# Sheet.net
KiCad netlist of a schematic drawn in Altium Designer
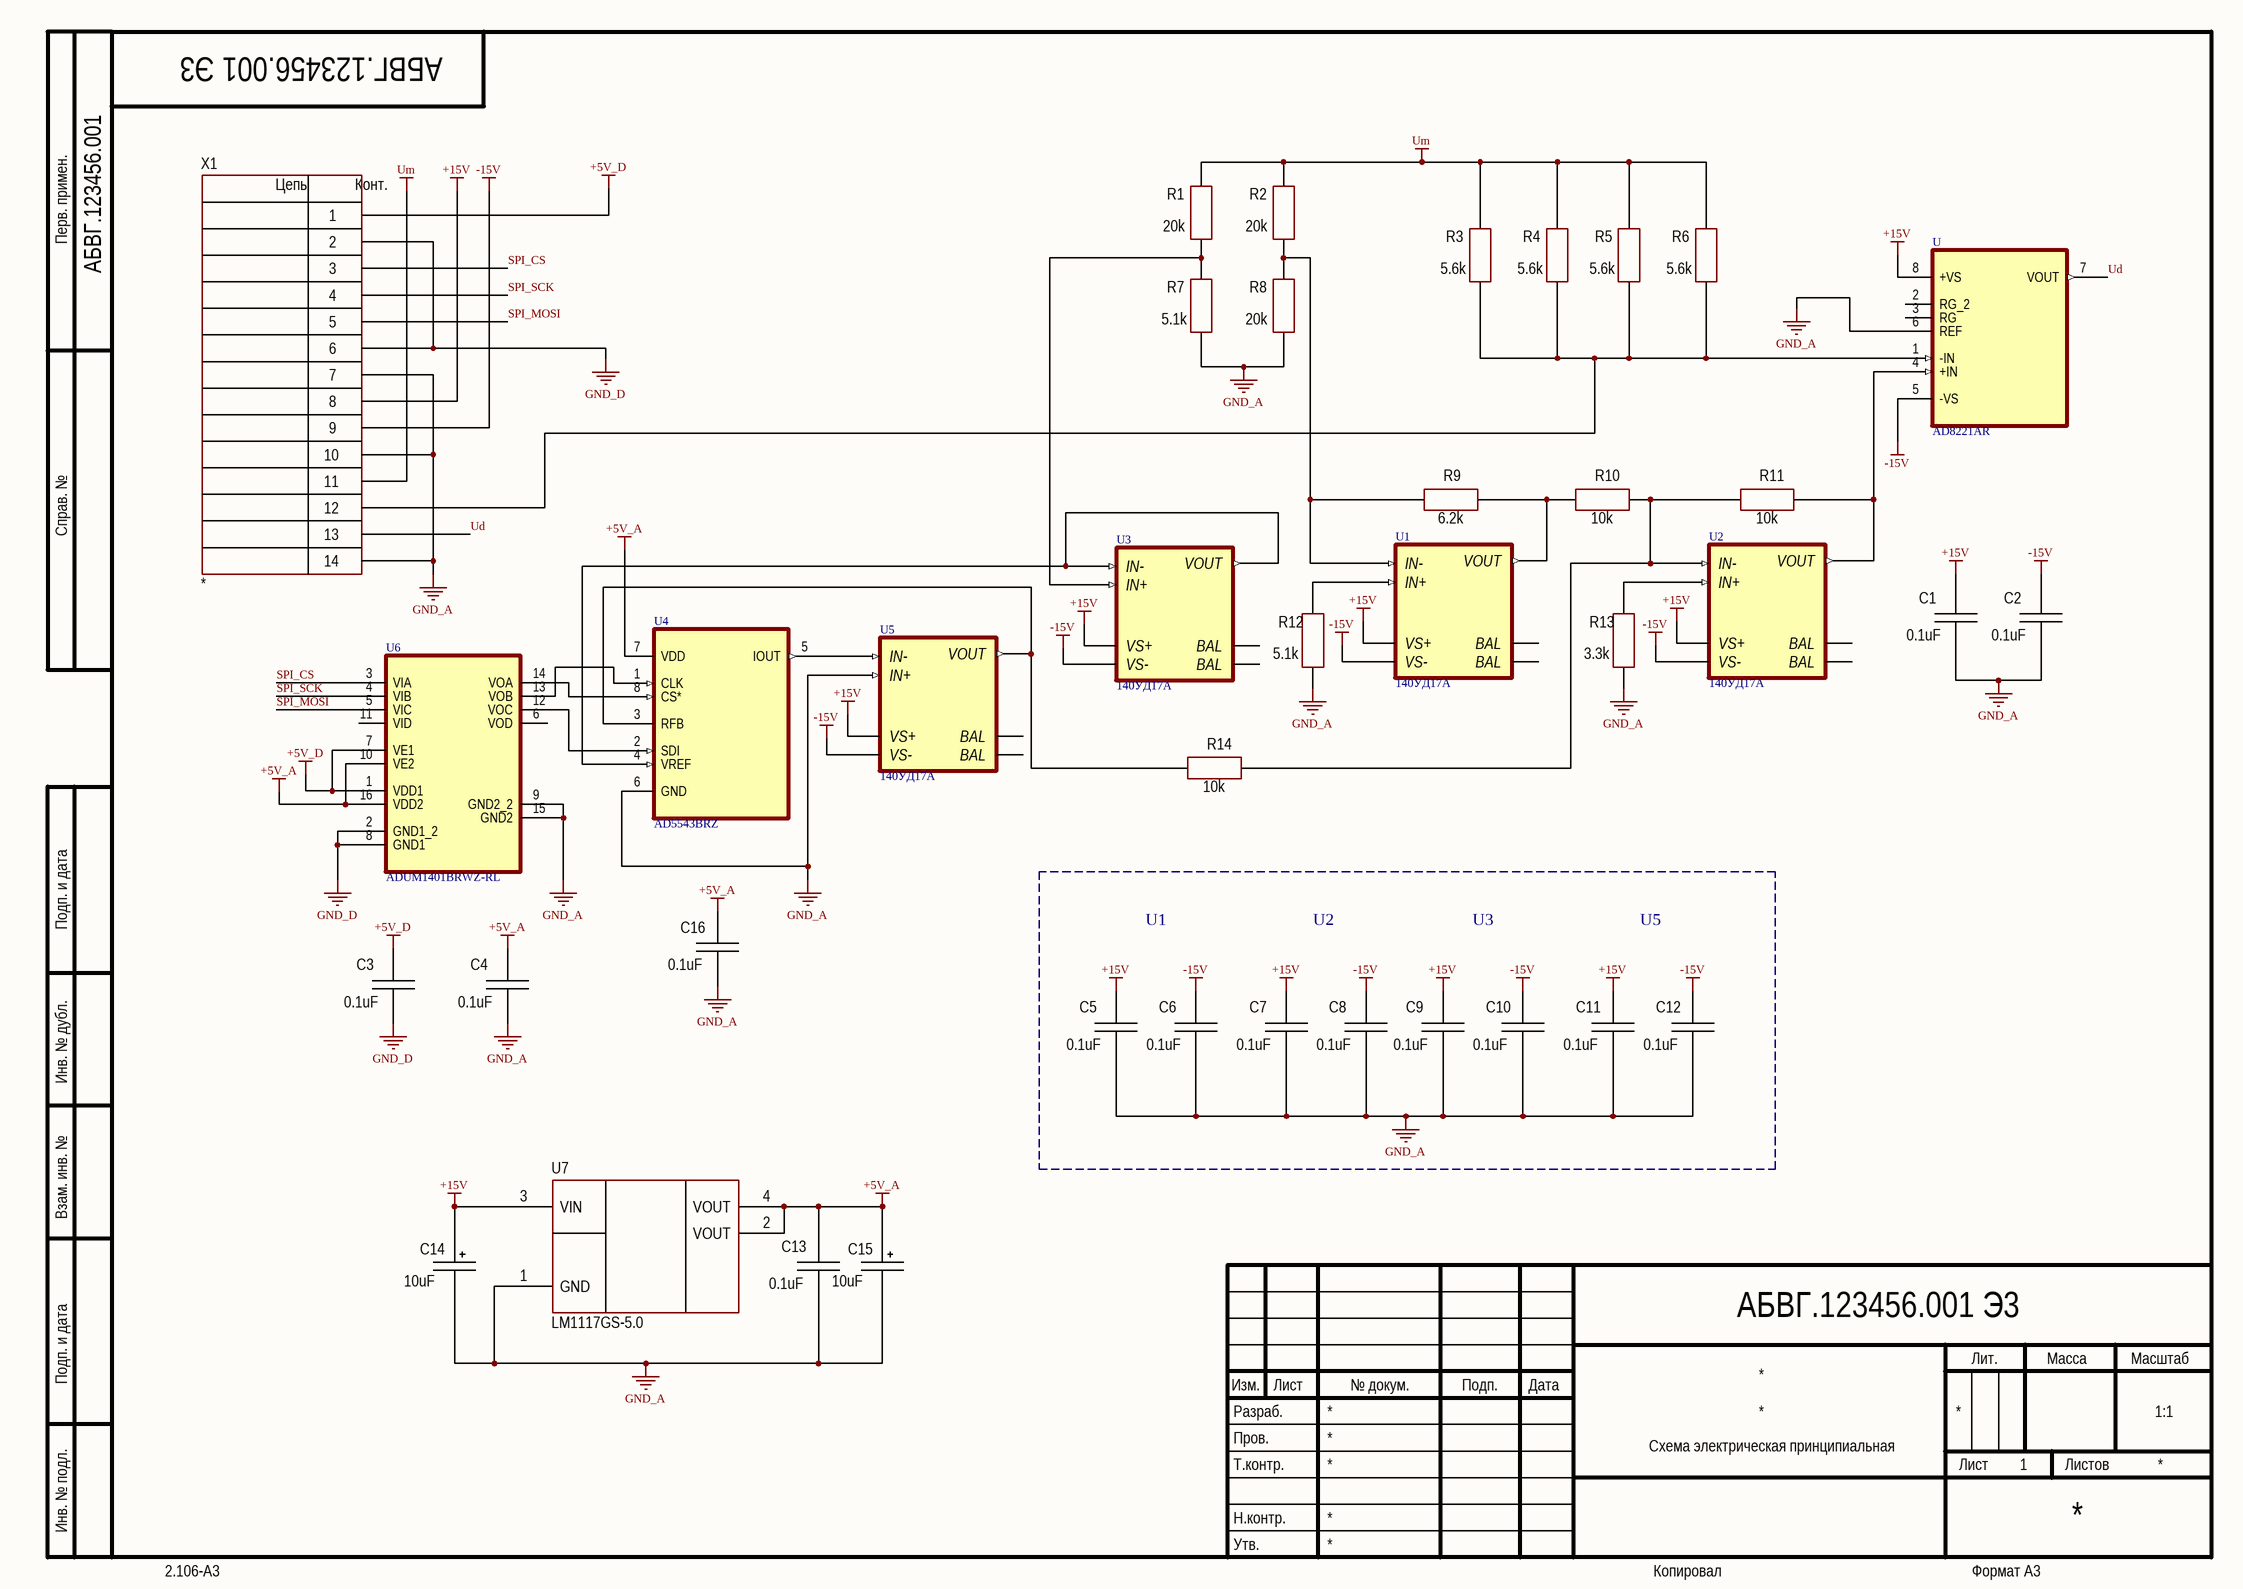
[diagram p0: Sheet.SchDoc]

(export (version "E")
  (design (tool "Eeschema 10.0.6"))
  (components
    (comp (ref "C1")
      (value "0.1uF")
      (footprint "standard:CH1206C")
      (libsource (lib "Discrete") (part "Capacitor"))
    )
    (comp (ref "C2")
      (value "0.1uF")
      (footprint "standard:CH1206C")
      (libsource (lib "Discrete") (part "Capacitor"))
    )
    (comp (ref "C3")
      (value "0.1uF")
      (footprint "standard:CH1206C")
      (libsource (lib "Discrete") (part "Capacitor"))
    )
    (comp (ref "C4")
      (value "0.1uF")
      (footprint "standard:CH1206C")
      (libsource (lib "Discrete") (part "Capacitor"))
    )
    (comp (ref "C5")
      (value "0.1uF")
      (footprint "standard:CH1206C")
      (libsource (lib "Discrete") (part "Capacitor"))
    )
    (comp (ref "C6")
      (value "0.1uF")
      (footprint "standard:CH1206C")
      (libsource (lib "Discrete") (part "Capacitor"))
    )
    (comp (ref "C7")
      (value "0.1uF")
      (footprint "standard:CH1206C")
      (libsource (lib "Discrete") (part "Capacitor"))
    )
    (comp (ref "C8")
      (value "0.1uF")
      (footprint "standard:CH1206C")
      (libsource (lib "Discrete") (part "Capacitor"))
    )
    (comp (ref "C9")
      (value "0.1uF")
      (footprint "standard:CH1206C")
      (libsource (lib "Discrete") (part "Capacitor"))
    )
    (comp (ref "C10")
      (value "0.1uF")
      (footprint "standard:CH1206C")
      (libsource (lib "Discrete") (part "Capacitor"))
    )
    (comp (ref "C11")
      (value "0.1uF")
      (footprint "standard:CH1206C")
      (libsource (lib "Discrete") (part "Capacitor"))
    )
    (comp (ref "C12")
      (value "0.1uF")
      (footprint "standard:CH1206C")
      (libsource (lib "Discrete") (part "Capacitor"))
    )
    (comp (ref "C13")
      (value "0.1uF")
      (footprint "standard:CH1206C")
      (libsource (lib "Discrete") (part "Capacitor"))
    )
    (comp (ref "C14")
      (value "10uF")
      (footprint "standard:TANTAL_A")
      (libsource (lib "Discrete") (part "TantalCap"))
    )
    (comp (ref "C15")
      (value "10uF")
      (footprint "standard:TANTAL_A")
      (libsource (lib "Discrete") (part "TantalCap"))
    )
    (comp (ref "C16")
      (value "0.1uF")
      (footprint "standard:CH1206C")
      (libsource (lib "Discrete") (part "Capacitor"))
    )
    (comp (ref "R1") (value "20k") (footprint "standard:CH1206R") (libsource (lib "") (part "Resistor_2")))
    (comp (ref "R2") (value "20k") (footprint "standard:CH1206R") (libsource (lib "") (part "Resistor_2")))
    (comp (ref "R3") (value "5.6k") (footprint "standard:CH1206R") (libsource (lib "") (part "Resistor_1")))
    (comp (ref "R4") (value "5.6k") (footprint "standard:CH1206R") (libsource (lib "") (part "Resistor_1")))
    (comp (ref "R5") (value "5.6k") (footprint "standard:CH1206R") (libsource (lib "") (part "Resistor_1")))
    (comp (ref "R6") (value "5.6k") (footprint "standard:CH1206R") (libsource (lib "") (part "Resistor_1")))
    (comp (ref "R7")
      (value "5.1k")
      (footprint "standard:CH1206R")
      (libsource (lib "Discrete") (part "Resistor"))
    )
    (comp (ref "R8")
      (value "20k")
      (footprint "standard:CH1206R")
      (libsource (lib "Discrete") (part "Resistor"))
    )
    (comp (ref "R9") (value "6.2k") (footprint "standard:CH1206R") (libsource (lib "") (part "Resistor_3")))
    (comp (ref "R10") (value "10k") (footprint "standard:CH1206R") (libsource (lib "") (part "Resistor_3")))
    (comp (ref "R11") (value "10k") (footprint "standard:CH1206R") (libsource (lib "") (part "Resistor_3")))
    (comp (ref "R12") (value "5.1k") (footprint "standard:CH1206R") (libsource (lib "") (part "Resistor_2")))
    (comp (ref "R13") (value "3.3k") (footprint "standard:CH1206R") (libsource (lib "") (part "Resistor_2")))
    (comp (ref "R14") (value "10k") (footprint "standard:CH1206R") (libsource (lib "") (part "Resistor_3")))
    (comp (ref "U")
      (value "AD8221AR")
      (footprint "SOIC127P600X175-8N")
      (description "Instrumentation Amplifier 1 Circuit 8-SOIC")
      (fields (field (name "MF") "Analog Devices") (field (name "MP") "AD8221BR"))
      (libsource (lib "AD8221BR") (part "AD8221BR"))
    )
    (comp (ref "U1")
      (value "140УД17А")
      (footprint "140УД17А")
      (description "Precision Op Amp")
      (libsource (lib "140УД17А") (part "140УД17А"))
    )
    (comp (ref "U2")
      (value "140УД17А")
      (footprint "140УД17А")
      (description "Precision Op Amp")
      (libsource (lib "") (part "140УД17А_1"))
    )
    (comp (ref "U3")
      (value "140УД17А")
      (footprint "140УД17А")
      (description "Precision Op Amp")
      (libsource (lib "") (part "140УД17А_1"))
    )
    (comp (ref "U4")
      (value "AD5543BRZ")
      (footprint "SOIC127P600X175-8N")
      (description "16 Bit Digital to Analog Converter 1 8-SOIC")
      (fields (field (name "MF") "Analog Devices"))
      (libsource (lib "AD5543BRZ") (part "AD5543BRZ"))
    )
    (comp (ref "U5")
      (value "140УД17А")
      (footprint "140УД17А")
      (description "Precision Op Amp")
      (libsource (lib "") (part "140УД17А_1"))
    )
    (comp (ref "U6")
      (value "ADUM1401BRWZ-RL")
      (footprint "SOIC127P1032X265-16N")
      (fields (field (name "MF") "Analog Devices"))
      (libsource (lib "ADUM1401BRWZ-RL") (part "ADUM1401BRWZ-RL"))
    )
    (comp (ref "U7")
      (value "~")
      (footprint "StandardCase:SOT223")
      (description "Linear voltage regulator")
      (fields
        (field (name "MANUFACTURER") "STMicroelectronics")
        (field (name "VALUEMANUFACTURERPARTNUMBER") "Linear voltage regulator, input 3.9...18V, 0.6V, output 3.3V, 1.2A, -40...+85°C, SOT223")
        (field (name "PARTNUMBER") "LM1117GS-5.0")
      )
      (libsource (lib "IC. Power supply") (part "LDL1117S33R"))
    )
    (comp (ref "X1")
      (value "*")
      (footprint "custom:CON: PLS-14")
      (libsource (lib "Connectors") (part "14-Connector"))
    )
  )
  (nets
    (net (code "1") (name "+5V_A") (class "Default")
      (node (ref "C13") (pin "2") (pinfunction "2_2") (pintype "power_in"))
      (node (ref "C15") (pin "1") (pinfunction "1_1") (pintype "power_in"))
      (node (ref "C16") (pin "2") (pinfunction "2_2") (pintype "power_in"))
      (node (ref "C4") (pin "2") (pinfunction "2_2") (pintype "power_in"))
      (node (ref "U4") (pin "7") (pinfunction "VDD_7") (pintype "power_in"))
      (node (ref "U6") (pin "10") (pinfunction "VE2_10") (pintype "passive"))
      (node (ref "U6") (pin "16") (pinfunction "VDD2_16") (pintype "power_in"))
      (node (ref "U7") (pin "2") (pinfunction "VOUT_2") (pintype "power_in"))
      (node (ref "U7") (pin "4") (pinfunction "VOUT_4") (pintype "power_in"))
    )
    (net (code "2") (name "+5V_D") (class "Default")
      (node (ref "C3") (pin "2") (pinfunction "2_2") (pintype "power_in"))
      (node (ref "U6") (pin "1") (pinfunction "VDD1_1") (pintype "power_in"))
      (node (ref "U6") (pin "7") (pinfunction "VE1_7") (pintype "passive"))
      (node (ref "X1") (pin "1") (pinfunction "1_1") (pintype "passive"))
    )
    (net (code "3") (name "+15V") (class "Default")
      (node (ref "C1") (pin "2") (pinfunction "2_2") (pintype "power_in"))
      (node (ref "C11") (pin "2") (pinfunction "2_2") (pintype "power_in"))
      (node (ref "C14") (pin "1") (pinfunction "1_1") (pintype "power_in"))
      (node (ref "C5") (pin "2") (pinfunction "2_2") (pintype "power_in"))
      (node (ref "C7") (pin "2") (pinfunction "2_2") (pintype "power_in"))
      (node (ref "C9") (pin "2") (pinfunction "2_2") (pintype "power_in"))
      (node (ref "U") (pin "8") (pinfunction "+VS_8") (pintype "power_in"))
      (node (ref "U1") (pin "8") (pinfunction "VS+_8") (pintype "power_in"))
      (node (ref "U2") (pin "8") (pinfunction "VS+_8") (pintype "power_in"))
      (node (ref "U3") (pin "8") (pinfunction "VS+_8") (pintype "power_in"))
      (node (ref "U5") (pin "8") (pinfunction "VS+_8") (pintype "power_in"))
      (node (ref "U7") (pin "3") (pinfunction "VIN_3") (pintype "power_in"))
      (node (ref "X1") (pin "8") (pinfunction "8_8") (pintype "power_in"))
    )
    (net (code "4") (name "-15V") (class "Default")
      (node (ref "C10") (pin "2") (pinfunction "2_2") (pintype "power_in"))
      (node (ref "C12") (pin "2") (pinfunction "2_2") (pintype "power_in"))
      (node (ref "C2") (pin "2") (pinfunction "2_2") (pintype "power_in"))
      (node (ref "C6") (pin "2") (pinfunction "2_2") (pintype "power_in"))
      (node (ref "C8") (pin "2") (pinfunction "2_2") (pintype "power_in"))
      (node (ref "U") (pin "5") (pinfunction "-VS_5") (pintype "power_in"))
      (node (ref "U1") (pin "5") (pinfunction "VS-_5") (pintype "power_in"))
      (node (ref "U2") (pin "5") (pinfunction "VS-_5") (pintype "power_in"))
      (node (ref "U3") (pin "5") (pinfunction "VS-_5") (pintype "power_in"))
      (node (ref "U5") (pin "5") (pinfunction "VS-_5") (pintype "power_in"))
      (node (ref "X1") (pin "9") (pinfunction "9_9") (pintype "power_in"))
    )
    (net (code "5") (name "/SPI_CS") (class "Default")
      (node (ref "U6") (pin "3") (pinfunction "VIA_3") (pintype "passive"))
      (node (ref "X1") (pin "3") (pinfunction "3_3") (pintype "power_in"))
    )
    (net (code "6") (name "/SPI_MOSI") (class "Default")
      (node (ref "U6") (pin "5") (pinfunction "VIC_5") (pintype "passive"))
      (node (ref "X1") (pin "5") (pinfunction "5_5") (pintype "power_in"))
    )
    (net (code "7") (name "/SPI_SCK") (class "Default")
      (node (ref "U6") (pin "4") (pinfunction "VIB_4") (pintype "passive"))
      (node (ref "X1") (pin "4") (pinfunction "4_4") (pintype "power_in"))
    )
    (net (code "8") (name "/Ud") (class "Default")
      (node (ref "U") (pin "7") (pinfunction "VOUT_7") (pintype "output"))
      (node (ref "X1") (pin "13") (pinfunction "13_13") (pintype "power_in"))
    )
    (net (code "9") (name "GND_A") (class "Default")
      (node (ref "C1") (pin "1") (pinfunction "1_1") (pintype "power_in"))
      (node (ref "C10") (pin "1") (pinfunction "1_1") (pintype "power_in"))
      (node (ref "C11") (pin "1") (pinfunction "1_1") (pintype "power_in"))
      (node (ref "C12") (pin "1") (pinfunction "1_1") (pintype "power_in"))
      (node (ref "C13") (pin "1") (pinfunction "1_1") (pintype "power_in"))
      (node (ref "C14") (pin "2") (pinfunction "2_2") (pintype "power_in"))
      (node (ref "C15") (pin "2") (pinfunction "2_2") (pintype "power_in"))
      (node (ref "C16") (pin "1") (pinfunction "1_1") (pintype "power_in"))
      (node (ref "C2") (pin "1") (pinfunction "1_1") (pintype "power_in"))
      (node (ref "C4") (pin "1") (pinfunction "1_1") (pintype "power_in"))
      (node (ref "C5") (pin "1") (pinfunction "1_1") (pintype "power_in"))
      (node (ref "C6") (pin "1") (pinfunction "1_1") (pintype "power_in"))
      (node (ref "C7") (pin "1") (pinfunction "1_1") (pintype "power_in"))
      (node (ref "C8") (pin "1") (pinfunction "1_1") (pintype "power_in"))
      (node (ref "C9") (pin "1") (pinfunction "1_1") (pintype "power_in"))
      (node (ref "R12") (pin "1") (pinfunction "1_1") (pintype "passive"))
      (node (ref "R13") (pin "1") (pinfunction "1_1") (pintype "passive"))
      (node (ref "R7") (pin "1") (pinfunction "1_1") (pintype "passive"))
      (node (ref "R8") (pin "1") (pinfunction "1_1") (pintype "passive"))
      (node (ref "U") (pin "6") (pinfunction "REF_6") (pintype "passive"))
      (node (ref "U4") (pin "6") (pinfunction "GND_6") (pintype "passive"))
      (node (ref "U5") (pin "4") (pinfunction "IN+_4") (pintype "input"))
      (node (ref "U6") (pin "15") (pinfunction "GND2_15") (pintype "passive"))
      (node (ref "U6") (pin "9") (pinfunction "GND2_2_9") (pintype "passive"))
      (node (ref "U7") (pin "1") (pinfunction "GND_1") (pintype "power_in"))
      (node (ref "X1") (pin "10") (pinfunction "10_10") (pintype "power_in"))
      (node (ref "X1") (pin "14") (pinfunction "14_14") (pintype "power_in"))
      (node (ref "X1") (pin "7") (pinfunction "7_7") (pintype "power_in"))
    )
    (net (code "10") (name "GND_D") (class "Default")
      (node (ref "C3") (pin "1") (pinfunction "1_1") (pintype "power_in"))
      (node (ref "U6") (pin "2") (pinfunction "GND1_2_2") (pintype "passive"))
      (node (ref "U6") (pin "8") (pinfunction "GND1_8") (pintype "passive"))
      (node (ref "X1") (pin "2") (pinfunction "2_2") (pintype "passive"))
      (node (ref "X1") (pin "6") (pinfunction "6_6") (pintype "power_in"))
    )
    (net (code "11") (name "Net-(U-+IN)") (class "Default")
      (node (ref "R11") (pin "2") (pinfunction "2_2") (pintype "passive"))
      (node (ref "U") (pin "4") (pinfunction "+IN_4") (pintype "input"))
      (node (ref "U2") (pin "7") (pinfunction "VOUT_7") (pintype "output"))
    )
    (net (code "12") (name "Net-(U--IN)") (class "Default")
      (node (ref "R3") (pin "1") (pinfunction "1_1") (pintype "passive"))
      (node (ref "R4") (pin "1") (pinfunction "1_1") (pintype "passive"))
      (node (ref "R5") (pin "1") (pinfunction "1_1") (pintype "passive"))
      (node (ref "R6") (pin "1") (pinfunction "1_1") (pintype "passive"))
      (node (ref "U") (pin "1") (pinfunction "-IN_1") (pintype "input"))
      (node (ref "X1") (pin "12") (pinfunction "12_12") (pintype "power_in"))
    )
    (net (code "13") (name "Net-(U1-IN+)") (class "Default")
      (node (ref "R12") (pin "2") (pinfunction "2_2") (pintype "passive"))
      (node (ref "U1") (pin "4") (pinfunction "IN+_4") (pintype "input"))
    )
    (net (code "14") (name "Net-(U1-IN-)") (class "Default")
      (node (ref "R2") (pin "1") (pinfunction "1_1") (pintype "passive"))
      (node (ref "R8") (pin "2") (pinfunction "2_2") (pintype "passive"))
      (node (ref "R9") (pin "1") (pinfunction "1_1") (pintype "passive"))
      (node (ref "U1") (pin "3") (pinfunction "IN-_3") (pintype "input"))
    )
    (net (code "15") (name "Net-(U1-VOUT)") (class "Default")
      (node (ref "R10") (pin "1") (pinfunction "1_1") (pintype "passive"))
      (node (ref "R9") (pin "2") (pinfunction "2_2") (pintype "passive"))
      (node (ref "U1") (pin "7") (pinfunction "VOUT_7") (pintype "output"))
    )
    (net (code "16") (name "Net-(U2-IN+)") (class "Default")
      (node (ref "R13") (pin "2") (pinfunction "2_2") (pintype "passive"))
      (node (ref "U2") (pin "4") (pinfunction "IN+_4") (pintype "input"))
    )
    (net (code "17") (name "Net-(U2-IN-)") (class "Default")
      (node (ref "R10") (pin "2") (pinfunction "2_2") (pintype "passive"))
      (node (ref "R11") (pin "1") (pinfunction "1_1") (pintype "passive"))
      (node (ref "R14") (pin "2") (pinfunction "2_2") (pintype "passive"))
      (node (ref "U2") (pin "3") (pinfunction "IN-_3") (pintype "input"))
    )
    (net (code "18") (name "Net-(U3-IN+)") (class "Default")
      (node (ref "R1") (pin "1") (pinfunction "1_1") (pintype "passive"))
      (node (ref "R7") (pin "2") (pinfunction "2_2") (pintype "passive"))
      (node (ref "U3") (pin "4") (pinfunction "IN+_4") (pintype "input"))
    )
    (net (code "19") (name "Net-(U3-IN-)") (class "Default")
      (node (ref "U3") (pin "3") (pinfunction "IN-_3") (pintype "input"))
      (node (ref "U3") (pin "7") (pinfunction "VOUT_7") (pintype "output"))
      (node (ref "U4") (pin "4") (pinfunction "VREF_4") (pintype "input"))
    )
    (net (code "20") (name "Net-(U4-CLK)") (class "Default")
      (node (ref "U4") (pin "1") (pinfunction "CLK_1") (pintype "input"))
      (node (ref "U6") (pin "13") (pinfunction "VOB_13") (pintype "passive"))
    )
    (net (code "21") (name "Net-(U4-CS*)") (class "Default")
      (node (ref "U4") (pin "8") (pinfunction "CS*_8") (pintype "input"))
      (node (ref "U6") (pin "14") (pinfunction "VOA_14") (pintype "passive"))
    )
    (net (code "22") (name "Net-(U4-IOUT)") (class "Default")
      (node (ref "U4") (pin "5") (pinfunction "IOUT_5") (pintype "output"))
      (node (ref "U5") (pin "3") (pinfunction "IN-_3") (pintype "input"))
    )
    (net (code "23") (name "Net-(U4-RFB)") (class "Default")
      (node (ref "R14") (pin "1") (pinfunction "1_1") (pintype "passive"))
      (node (ref "U4") (pin "3") (pinfunction "RFB_3") (pintype "passive"))
      (node (ref "U5") (pin "7") (pinfunction "VOUT_7") (pintype "output"))
    )
    (net (code "24") (name "Net-(U4-SDI)") (class "Default")
      (node (ref "U4") (pin "2") (pinfunction "SDI_2") (pintype "input"))
      (node (ref "U6") (pin "12") (pinfunction "VOC_12") (pintype "passive"))
    )
    (net (code "25") (name "Um") (class "Default")
      (node (ref "R1") (pin "2") (pinfunction "2_2") (pintype "passive"))
      (node (ref "R2") (pin "2") (pinfunction "2_2") (pintype "passive"))
      (node (ref "R3") (pin "2") (pinfunction "2_2") (pintype "passive"))
      (node (ref "R4") (pin "2") (pinfunction "2_2") (pintype "passive"))
      (node (ref "R5") (pin "2") (pinfunction "2_2") (pintype "passive"))
      (node (ref "R6") (pin "2") (pinfunction "2_2") (pintype "passive"))
      (node (ref "X1") (pin "11") (pinfunction "11_11") (pintype "power_in"))
    )
    (net (code "26") (name "unconnected-(U-RG-Pad3)") (class "Default")
      (node (ref "U") (pin "3") (pinfunction "RG_3") (pintype "passive"))
    )
    (net (code "27") (name "unconnected-(U-RG_2-Pad2)") (class "Default")
      (node (ref "U") (pin "2") (pinfunction "RG_2_2") (pintype "passive"))
    )
    (net (code "28") (name "unconnected-(U1-BAL-Pad1)") (class "Default")
      (node (ref "U1") (pin "1") (pinfunction "BAL_1") (pintype "passive"))
    )
    (net (code "29") (name "unconnected-(U1-BAL-Pad2)") (class "Default")
      (node (ref "U1") (pin "2") (pinfunction "BAL_2") (pintype "passive"))
    )
    (net (code "30") (name "unconnected-(U2-BAL-Pad1)") (class "Default")
      (node (ref "U2") (pin "1") (pinfunction "BAL_1") (pintype "passive"))
    )
    (net (code "31") (name "unconnected-(U2-BAL-Pad2)") (class "Default")
      (node (ref "U2") (pin "2") (pinfunction "BAL_2") (pintype "passive"))
    )
    (net (code "32") (name "unconnected-(U3-BAL-Pad1)") (class "Default")
      (node (ref "U3") (pin "1") (pinfunction "BAL_1") (pintype "passive"))
    )
    (net (code "33") (name "unconnected-(U3-BAL-Pad2)") (class "Default")
      (node (ref "U3") (pin "2") (pinfunction "BAL_2") (pintype "passive"))
    )
    (net (code "34") (name "unconnected-(U5-BAL-Pad1)") (class "Default")
      (node (ref "U5") (pin "1") (pinfunction "BAL_1") (pintype "passive"))
    )
    (net (code "35") (name "unconnected-(U5-BAL-Pad2)") (class "Default")
      (node (ref "U5") (pin "2") (pinfunction "BAL_2") (pintype "passive"))
    )
    (net (code "36") (name "unconnected-(U6-VID-Pad11)") (class "Default")
      (node (ref "U6") (pin "11") (pinfunction "VID_11") (pintype "passive"))
    )
    (net (code "37") (name "unconnected-(U6-VOD-Pad6)") (class "Default")
      (node (ref "U6") (pin "6") (pinfunction "VOD_6") (pintype "passive"))
    )
  )
)
